# Tugas2.net
KiCad netlist of a schematic drawn in EAGLE
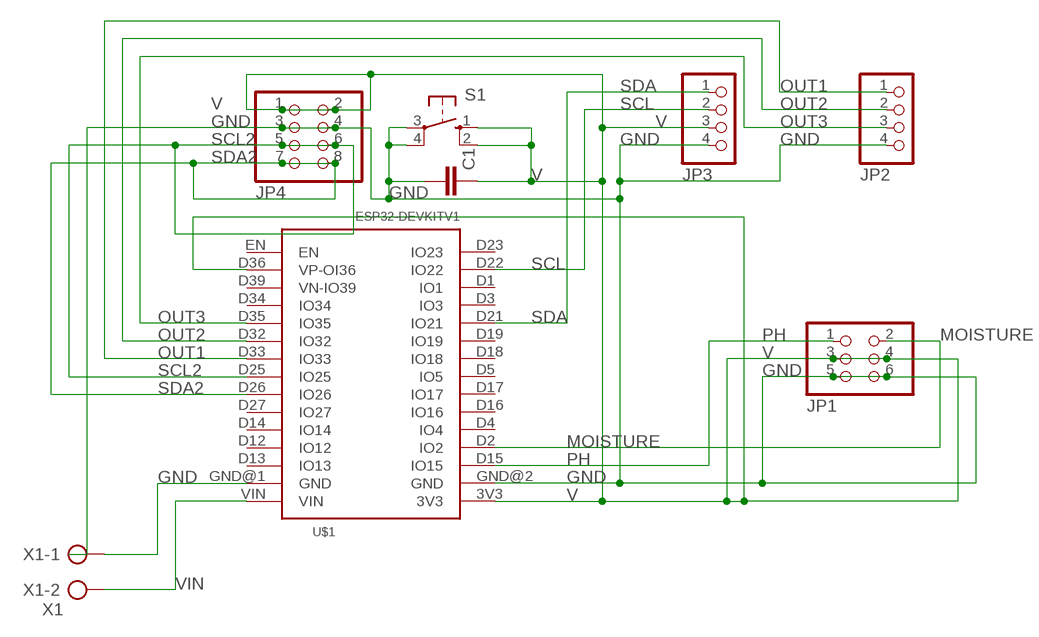
[diagram p0: schematic, sheet 1]

(export (version "E")
  (design (tool "Eeschema 10.0.6"))
  (components
    (comp (ref "C1")
      (value "C1")
      (footprint "eagle-import:C050-030X075")
      (libsource (lib "eagle-import") (part "C-EU050-030X075"))
    )
    (comp (ref "JP1")
      (value "JP1")
      (footprint "eagle-import:2X03")
      (libsource (lib "eagle-import") (part "PINHD-2X3"))
    )
    (comp (ref "JP2")
      (value "JP2")
      (footprint "eagle-import:1X04")
      (libsource (lib "eagle-import") (part "PINHD-1X4"))
    )
    (comp (ref "JP3")
      (value "JP3")
      (footprint "eagle-import:1X04")
      (libsource (lib "eagle-import") (part "PINHD-1X4"))
    )
    (comp (ref "JP4")
      (value "JP4")
      (footprint "eagle-import:2X04")
      (libsource (lib "eagle-import") (part "PINHD-2X4"))
    )
    (comp (ref "S1")
      (value "S1")
      (footprint "eagle-import:B3F-10XX")
      (fields (field (name "MPN") "B3F-1000"))
      (libsource (lib "eagle-import") (part "10-XX"))
    )
    (comp (ref "U$1")
      (value "ESP32DEVKITV1")
      (footprint "eagle-import:ESP32-DEVKITV1")
      (libsource (lib "eagle-import") (part "ESP32DEVKITV1"))
    )
    (comp (ref "X1")
      (value "X1")
      (footprint "eagle-import:AK300_2")
      (libsource (lib "eagle-import") (part "AK300/2"))
    )
  )
  (nets
    (net (code "1") (name "/GND") (class "Default")
      (node (ref "C1") (pin "1") (pinfunction "1_1") (pintype "passive"))
      (node (ref "JP1") (pin "5") (pinfunction "5_5") (pintype "passive"))
      (node (ref "JP1") (pin "6") (pinfunction "6_6") (pintype "passive"))
      (node (ref "JP2") (pin "4") (pinfunction "4_4") (pintype "passive"))
      (node (ref "JP3") (pin "4") (pinfunction "4_4") (pintype "passive"))
      (node (ref "JP4") (pin "3") (pinfunction "3_3") (pintype "passive"))
      (node (ref "JP4") (pin "4") (pinfunction "4_4") (pintype "passive"))
      (node (ref "S1") (pin "3") (pinfunction "P_3") (pintype "passive"))
      (node (ref "S1") (pin "4") (pinfunction "P1_4") (pintype "passive"))
      (node (ref "U$1") (pin "GND@1") (pinfunction "GND_GND@1") (pintype "bidirectional"))
      (node (ref "U$1") (pin "GND@2") (pinfunction "GND_GND@2") (pintype "bidirectional"))
      (node (ref "X1") (pin "1") (pinfunction "KL_1") (pintype "passive"))
    )
    (net (code "2") (name "/MOISTURE") (class "Default")
      (node (ref "JP1") (pin "2") (pinfunction "2_2") (pintype "passive"))
      (node (ref "U$1") (pin "D2") (pinfunction "IO2_D2") (pintype "bidirectional"))
    )
    (net (code "3") (name "/OUT1") (class "Default")
      (node (ref "JP2") (pin "1") (pinfunction "1_1") (pintype "passive"))
      (node (ref "U$1") (pin "D33") (pinfunction "IO33_D33") (pintype "bidirectional"))
    )
    (net (code "4") (name "/OUT2") (class "Default")
      (node (ref "JP2") (pin "2") (pinfunction "2_2") (pintype "passive"))
      (node (ref "U$1") (pin "D32") (pinfunction "IO32_D32") (pintype "bidirectional"))
    )
    (net (code "5") (name "/OUT3") (class "Default")
      (node (ref "JP2") (pin "3") (pinfunction "3_3") (pintype "passive"))
      (node (ref "U$1") (pin "D35") (pinfunction "IO35_D35") (pintype "bidirectional"))
    )
    (net (code "6") (name "/PH") (class "Default")
      (node (ref "JP1") (pin "1") (pinfunction "1_1") (pintype "passive"))
      (node (ref "U$1") (pin "D15") (pinfunction "IO15_D15") (pintype "bidirectional"))
    )
    (net (code "7") (name "/SCL") (class "Default")
      (node (ref "JP3") (pin "2") (pinfunction "2_2") (pintype "passive"))
      (node (ref "U$1") (pin "D22") (pinfunction "IO22_D22") (pintype "bidirectional"))
    )
    (net (code "8") (name "/SCL2") (class "Default")
      (node (ref "JP4") (pin "5") (pinfunction "5_5") (pintype "passive"))
      (node (ref "JP4") (pin "6") (pinfunction "6_6") (pintype "passive"))
      (node (ref "U$1") (pin "D25") (pinfunction "IO25_D25") (pintype "bidirectional"))
    )
    (net (code "9") (name "/SDA") (class "Default")
      (node (ref "JP3") (pin "1") (pinfunction "1_1") (pintype "passive"))
      (node (ref "U$1") (pin "D21") (pinfunction "IO21_D21") (pintype "bidirectional"))
    )
    (net (code "10") (name "/SDA2") (class "Default")
      (node (ref "JP4") (pin "7") (pinfunction "7_7") (pintype "passive"))
      (node (ref "JP4") (pin "8") (pinfunction "8_8") (pintype "passive"))
      (node (ref "U$1") (pin "D26") (pinfunction "IO26_D26") (pintype "bidirectional"))
    )
    (net (code "11") (name "/V") (class "Default")
      (node (ref "C1") (pin "2") (pinfunction "2_2") (pintype "passive"))
      (node (ref "JP1") (pin "3") (pinfunction "3_3") (pintype "passive"))
      (node (ref "JP1") (pin "4") (pinfunction "4_4") (pintype "passive"))
      (node (ref "JP3") (pin "3") (pinfunction "3_3") (pintype "passive"))
      (node (ref "JP4") (pin "1") (pinfunction "1_1") (pintype "passive"))
      (node (ref "JP4") (pin "2") (pinfunction "2_2") (pintype "passive"))
      (node (ref "S1") (pin "1") (pinfunction "S_1") (pintype "passive"))
      (node (ref "S1") (pin "2") (pinfunction "S1_2") (pintype "passive"))
      (node (ref "U$1") (pin "3V3") (pinfunction "3V3_3V3") (pintype "bidirectional"))
      (node (ref "U$1") (pin "D36") (pinfunction "VP-OI36_D36") (pintype "bidirectional"))
    )
    (net (code "12") (name "/VIN") (class "Default")
      (node (ref "U$1") (pin "VIN") (pinfunction "VIN_VIN") (pintype "bidirectional"))
      (node (ref "X1") (pin "2") (pinfunction "KL_2") (pintype "passive"))
    )
    (net (code "13") (name "unconnected-(U$1-IO1-PadD1)") (class "Default")
      (node (ref "U$1") (pin "D1") (pinfunction "IO1_D1") (pintype "bidirectional"))
    )
    (net (code "14") (name "unconnected-(U$1-IO3-PadD3)") (class "Default")
      (node (ref "U$1") (pin "D3") (pinfunction "IO3_D3") (pintype "bidirectional"))
    )
    (net (code "15") (name "unconnected-(U$1-IO4-PadD4)") (class "Default")
      (node (ref "U$1") (pin "D4") (pinfunction "IO4_D4") (pintype "bidirectional"))
    )
    (net (code "16") (name "unconnected-(U$1-IO5-PadD5)") (class "Default")
      (node (ref "U$1") (pin "D5") (pinfunction "IO5_D5") (pintype "bidirectional"))
    )
    (net (code "17") (name "unconnected-(U$1-IO12-PadD12)") (class "Default")
      (node (ref "U$1") (pin "D12") (pinfunction "IO12_D12") (pintype "bidirectional"))
    )
    (net (code "18") (name "unconnected-(U$1-IO13-PadD13)") (class "Default")
      (node (ref "U$1") (pin "D13") (pinfunction "IO13_D13") (pintype "bidirectional"))
    )
    (net (code "19") (name "unconnected-(U$1-IO14-PadD14)") (class "Default")
      (node (ref "U$1") (pin "D14") (pinfunction "IO14_D14") (pintype "bidirectional"))
    )
    (net (code "20") (name "unconnected-(U$1-IO16-PadD16)") (class "Default")
      (node (ref "U$1") (pin "D16") (pinfunction "IO16_D16") (pintype "bidirectional"))
    )
    (net (code "21") (name "unconnected-(U$1-IO17-PadD17)") (class "Default")
      (node (ref "U$1") (pin "D17") (pinfunction "IO17_D17") (pintype "bidirectional"))
    )
    (net (code "22") (name "unconnected-(U$1-IO18-PadD18)") (class "Default")
      (node (ref "U$1") (pin "D18") (pinfunction "IO18_D18") (pintype "bidirectional"))
    )
    (net (code "23") (name "unconnected-(U$1-IO19-PadD19)") (class "Default")
      (node (ref "U$1") (pin "D19") (pinfunction "IO19_D19") (pintype "bidirectional"))
    )
    (net (code "24") (name "unconnected-(U$1-IO23-PadD23)") (class "Default")
      (node (ref "U$1") (pin "D23") (pinfunction "IO23_D23") (pintype "bidirectional"))
    )
    (net (code "25") (name "unconnected-(U$1-IO27-PadD27)") (class "Default")
      (node (ref "U$1") (pin "D27") (pinfunction "IO27_D27") (pintype "bidirectional"))
    )
    (net (code "26") (name "unconnected-(U$1-IO34-PadD34)") (class "Default")
      (node (ref "U$1") (pin "D34") (pinfunction "IO34_D34") (pintype "bidirectional"))
    )
    (net (code "27") (name "unconnected-(U$1-PadEN)") (class "Default")
      (node (ref "U$1") (pin "EN") (pinfunction "EN_EN") (pintype "bidirectional"))
    )
    (net (code "28") (name "unconnected-(U$1-VN-IO39-PadD39)") (class "Default")
      (node (ref "U$1") (pin "D39") (pinfunction "VN-IO39_D39") (pintype "bidirectional"))
    )
  )
)
